# 1_Connector.net
KiCad netlist of a schematic drawn in Altium Designer
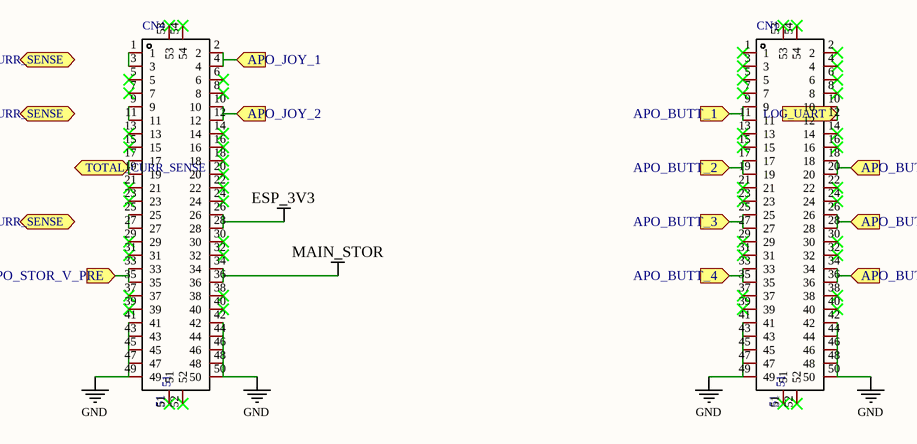
[diagram p0: 1_Connector.schdoc]

(export (version "E")
  (design (tool "Eeschema 10.0.6"))
  (components
    (comp (ref "CN1")
      (value "DF40C-50DP-0.4V(51)")
      (fields (field (name "MANUFACTURER") "HRS(广濑)") (field (name "NAME") "51") (field (name "NUMBER") "51"))
      (libsource (lib "altium-import") (part "root_0_DF40C-50DP-0.4V(51)_"))
    )
    (comp (ref "CN4")
      (value "DF40C-50DP-0.4V(51)")
      (fields (field (name "MANUFACTURER") "HRS(广濑)") (field (name "NAME") "51") (field (name "NUMBER") "51"))
      (libsource (lib "altium-import") (part "root_0_DF40C-50DP-0.4V(51)_"))
    )
  )
  (nets
    (net (code "1") (name "/APO_BUTT_1") (class "Default")
      (node (ref "CN1") (pin "11") (pinfunction "11_11") (pintype "passive"))
      (node (ref "CN1") (pin "9") (pinfunction "9_9") (pintype "passive"))
    )
    (net (code "2") (name "/APO_BUTT_2") (class "Default")
      (node (ref "CN1") (pin "17") (pinfunction "17_17") (pintype "passive"))
      (node (ref "CN1") (pin "19") (pinfunction "19_19") (pintype "passive"))
    )
    (net (code "3") (name "/APO_BUTT_3") (class "Default")
      (node (ref "CN1") (pin "25") (pinfunction "25_25") (pintype "passive"))
      (node (ref "CN1") (pin "27") (pinfunction "27_27") (pintype "passive"))
    )
    (net (code "4") (name "/APO_BUTT_4") (class "Default")
      (node (ref "CN1") (pin "33") (pinfunction "33_33") (pintype "passive"))
      (node (ref "CN1") (pin "35") (pinfunction "35_35") (pintype "passive"))
    )
    (net (code "5") (name "/APO_BUTT_5") (class "Default")
      (node (ref "CN1") (pin "34") (pinfunction "34_34") (pintype "passive"))
      (node (ref "CN1") (pin "36") (pinfunction "36_36") (pintype "passive"))
    )
    (net (code "6") (name "/APO_BUTT_6") (class "Default")
      (node (ref "CN1") (pin "26") (pinfunction "26_26") (pintype "passive"))
      (node (ref "CN1") (pin "28") (pinfunction "28_28") (pintype "passive"))
    )
    (net (code "7") (name "/APO_BUTT_7") (class "Default")
      (node (ref "CN1") (pin "18") (pinfunction "18_18") (pintype "passive"))
      (node (ref "CN1") (pin "20") (pinfunction "20_20") (pintype "passive"))
    )
    (net (code "8") (name "/APO_JOY_1") (class "Default")
      (node (ref "CN4") (pin "2") (pinfunction "2_2") (pintype "passive"))
      (node (ref "CN4") (pin "4") (pinfunction "4_4") (pintype "passive"))
    )
    (net (code "9") (name "/APO_JOY_2") (class "Default")
      (node (ref "CN4") (pin "10") (pinfunction "10_10") (pintype "passive"))
      (node (ref "CN4") (pin "12") (pinfunction "12_12") (pintype "passive"))
    )
    (net (code "10") (name "/APO_STOR_V_PRE") (class "Default")
      (node (ref "CN4") (pin "33") (pinfunction "33_33") (pintype "passive"))
      (node (ref "CN4") (pin "35") (pinfunction "35_35") (pintype "passive"))
    )
    (net (code "13") (name "/LOG_UART") (class "Default")
      (node (ref "CN1") (pin "10") (pinfunction "10_10") (pintype "passive"))
      (node (ref "CN1") (pin "12") (pinfunction "12_12") (pintype "passive"))
    )
    (net (code "16") (name "ESP_3V3") (class "Default")
      (node (ref "CN4") (pin "26") (pinfunction "26_26") (pintype "passive"))
      (node (ref "CN4") (pin "28") (pinfunction "28_28") (pintype "passive"))
    )
    (net (code "17") (name "GND") (class "Default")
      (node (ref "CN1") (pin "41") (pinfunction "41_41") (pintype "passive"))
      (node (ref "CN1") (pin "42") (pinfunction "42_42") (pintype "passive"))
      (node (ref "CN1") (pin "43") (pinfunction "43_43") (pintype "passive"))
      (node (ref "CN1") (pin "44") (pinfunction "44_44") (pintype "passive"))
      (node (ref "CN1") (pin "45") (pinfunction "45_45") (pintype "passive"))
      (node (ref "CN1") (pin "46") (pinfunction "46_46") (pintype "passive"))
      (node (ref "CN1") (pin "47") (pinfunction "47_47") (pintype "passive"))
      (node (ref "CN1") (pin "48") (pinfunction "48_48") (pintype "passive"))
      (node (ref "CN1") (pin "49") (pinfunction "49_49") (pintype "passive"))
      (node (ref "CN1") (pin "50") (pinfunction "50_50") (pintype "passive"))
      (node (ref "CN4") (pin "41") (pinfunction "41_41") (pintype "passive"))
      (node (ref "CN4") (pin "42") (pinfunction "42_42") (pintype "passive"))
      (node (ref "CN4") (pin "43") (pinfunction "43_43") (pintype "passive"))
      (node (ref "CN4") (pin "44") (pinfunction "44_44") (pintype "passive"))
      (node (ref "CN4") (pin "45") (pinfunction "45_45") (pintype "passive"))
      (node (ref "CN4") (pin "46") (pinfunction "46_46") (pintype "passive"))
      (node (ref "CN4") (pin "47") (pinfunction "47_47") (pintype "passive"))
      (node (ref "CN4") (pin "48") (pinfunction "48_48") (pintype "passive"))
      (node (ref "CN4") (pin "49") (pinfunction "49_49") (pintype "passive"))
      (node (ref "CN4") (pin "50") (pinfunction "50_50") (pintype "passive"))
    )
    (net (code "18") (name "MAIN_STOR") (class "Default")
      (node (ref "CN4") (pin "34") (pinfunction "34_34") (pintype "passive"))
      (node (ref "CN4") (pin "36") (pinfunction "36_36") (pintype "passive"))
    )
    (net (code "19") (name "Net-(CN4-Pad1)") (class "Default")
      (node (ref "CN4") (pin "1") (pinfunction "1_1") (pintype "passive"))
      (node (ref "CN4") (pin "3") (pinfunction "3_3") (pintype "passive"))
    )
    (net (code "20") (name "Net-(CN4-Pad11)") (class "Default")
      (node (ref "CN4") (pin "11") (pinfunction "11_11") (pintype "passive"))
      (node (ref "CN4") (pin "9") (pinfunction "9_9") (pintype "passive"))
    )
    (net (code "21") (name "Net-(CN4-Pad17)") (class "Default")
      (node (ref "CN4") (pin "17") (pinfunction "17_17") (pintype "passive"))
      (node (ref "CN4") (pin "19") (pinfunction "19_19") (pintype "passive"))
    )
    (net (code "22") (name "Net-(CN4-Pad25)") (class "Default")
      (node (ref "CN4") (pin "25") (pinfunction "25_25") (pintype "passive"))
      (node (ref "CN4") (pin "27") (pinfunction "27_27") (pintype "passive"))
    )
    (net (code "23") (name "unconnected-(CN1-Pad1)") (class "Default")
      (node (ref "CN1") (pin "1") (pinfunction "1_1") (pintype "passive+no_connect"))
    )
    (net (code "24") (name "unconnected-(CN1-Pad2)") (class "Default")
      (node (ref "CN1") (pin "2") (pinfunction "2_2") (pintype "passive+no_connect"))
    )
    (net (code "25") (name "unconnected-(CN1-Pad3)") (class "Default")
      (node (ref "CN1") (pin "3") (pinfunction "3_3") (pintype "passive+no_connect"))
    )
    (net (code "26") (name "unconnected-(CN1-Pad4)") (class "Default")
      (node (ref "CN1") (pin "4") (pinfunction "4_4") (pintype "passive+no_connect"))
    )
    (net (code "27") (name "unconnected-(CN1-Pad5)") (class "Default")
      (node (ref "CN1") (pin "5") (pinfunction "5_5") (pintype "passive+no_connect"))
    )
    (net (code "28") (name "unconnected-(CN1-Pad6)") (class "Default")
      (node (ref "CN1") (pin "6") (pinfunction "6_6") (pintype "passive+no_connect"))
    )
    (net (code "29") (name "unconnected-(CN1-Pad7)") (class "Default")
      (node (ref "CN1") (pin "7") (pinfunction "7_7") (pintype "passive+no_connect"))
    )
    (net (code "30") (name "unconnected-(CN1-Pad8)") (class "Default")
      (node (ref "CN1") (pin "8") (pinfunction "8_8") (pintype "passive+no_connect"))
    )
    (net (code "31") (name "unconnected-(CN1-Pad13)") (class "Default")
      (node (ref "CN1") (pin "13") (pinfunction "13_13") (pintype "passive+no_connect"))
    )
    (net (code "32") (name "unconnected-(CN1-Pad14)") (class "Default")
      (node (ref "CN1") (pin "14") (pinfunction "14_14") (pintype "passive+no_connect"))
    )
    (net (code "33") (name "unconnected-(CN1-Pad15)") (class "Default")
      (node (ref "CN1") (pin "15") (pinfunction "15_15") (pintype "passive+no_connect"))
    )
    (net (code "34") (name "unconnected-(CN1-Pad16)") (class "Default")
      (node (ref "CN1") (pin "16") (pinfunction "16_16") (pintype "passive+no_connect"))
    )
    (net (code "35") (name "unconnected-(CN1-Pad21)") (class "Default")
      (node (ref "CN1") (pin "21") (pinfunction "21_21") (pintype "passive+no_connect"))
    )
    (net (code "36") (name "unconnected-(CN1-Pad22)") (class "Default")
      (node (ref "CN1") (pin "22") (pinfunction "22_22") (pintype "passive+no_connect"))
    )
    (net (code "37") (name "unconnected-(CN1-Pad23)") (class "Default")
      (node (ref "CN1") (pin "23") (pinfunction "23_23") (pintype "passive+no_connect"))
    )
    (net (code "38") (name "unconnected-(CN1-Pad24)") (class "Default")
      (node (ref "CN1") (pin "24") (pinfunction "24_24") (pintype "passive+no_connect"))
    )
    (net (code "39") (name "unconnected-(CN1-Pad29)") (class "Default")
      (node (ref "CN1") (pin "29") (pinfunction "29_29") (pintype "passive+no_connect"))
    )
    (net (code "40") (name "unconnected-(CN1-Pad30)") (class "Default")
      (node (ref "CN1") (pin "30") (pinfunction "30_30") (pintype "passive+no_connect"))
    )
    (net (code "41") (name "unconnected-(CN1-Pad31)") (class "Default")
      (node (ref "CN1") (pin "31") (pinfunction "31_31") (pintype "passive+no_connect"))
    )
    (net (code "42") (name "unconnected-(CN1-Pad32)") (class "Default")
      (node (ref "CN1") (pin "32") (pinfunction "32_32") (pintype "passive+no_connect"))
    )
    (net (code "43") (name "unconnected-(CN1-Pad37)") (class "Default")
      (node (ref "CN1") (pin "37") (pinfunction "37_37") (pintype "passive+no_connect"))
    )
    (net (code "44") (name "unconnected-(CN1-Pad38)") (class "Default")
      (node (ref "CN1") (pin "38") (pinfunction "38_38") (pintype "passive+no_connect"))
    )
    (net (code "45") (name "unconnected-(CN1-Pad39)") (class "Default")
      (node (ref "CN1") (pin "39") (pinfunction "39_39") (pintype "passive+no_connect"))
    )
    (net (code "46") (name "unconnected-(CN1-Pad40)") (class "Default")
      (node (ref "CN1") (pin "40") (pinfunction "40_40") (pintype "passive+no_connect"))
    )
    (net (code "47") (name "unconnected-(CN1-Pad51)") (class "Default")
      (node (ref "CN1") (pin "51") (pinfunction "51_51") (pintype "passive+no_connect"))
    )
    (net (code "48") (name "unconnected-(CN1-Pad52)") (class "Default")
      (node (ref "CN1") (pin "52") (pinfunction "52_52") (pintype "passive+no_connect"))
    )
    (net (code "49") (name "unconnected-(CN1-Pad53)") (class "Default")
      (node (ref "CN1") (pin "53") (pinfunction "53_53") (pintype "passive+no_connect"))
    )
    (net (code "50") (name "unconnected-(CN1-Pad54)") (class "Default")
      (node (ref "CN1") (pin "54") (pinfunction "54_54") (pintype "passive+no_connect"))
    )
    (net (code "51") (name "unconnected-(CN4-Pad5)") (class "Default")
      (node (ref "CN4") (pin "5") (pinfunction "5_5") (pintype "passive+no_connect"))
    )
    (net (code "52") (name "unconnected-(CN4-Pad6)") (class "Default")
      (node (ref "CN4") (pin "6") (pinfunction "6_6") (pintype "passive+no_connect"))
    )
    (net (code "53") (name "unconnected-(CN4-Pad7)") (class "Default")
      (node (ref "CN4") (pin "7") (pinfunction "7_7") (pintype "passive+no_connect"))
    )
    (net (code "54") (name "unconnected-(CN4-Pad8)") (class "Default")
      (node (ref "CN4") (pin "8") (pinfunction "8_8") (pintype "passive+no_connect"))
    )
    (net (code "55") (name "unconnected-(CN4-Pad13)") (class "Default")
      (node (ref "CN4") (pin "13") (pinfunction "13_13") (pintype "passive+no_connect"))
    )
    (net (code "56") (name "unconnected-(CN4-Pad14)") (class "Default")
      (node (ref "CN4") (pin "14") (pinfunction "14_14") (pintype "passive+no_connect"))
    )
    (net (code "57") (name "unconnected-(CN4-Pad15)") (class "Default")
      (node (ref "CN4") (pin "15") (pinfunction "15_15") (pintype "passive+no_connect"))
    )
    (net (code "58") (name "unconnected-(CN4-Pad16)") (class "Default")
      (node (ref "CN4") (pin "16") (pinfunction "16_16") (pintype "passive+no_connect"))
    )
    (net (code "59") (name "unconnected-(CN4-Pad18)") (class "Default")
      (node (ref "CN4") (pin "18") (pinfunction "18_18") (pintype "passive+no_connect"))
    )
    (net (code "60") (name "unconnected-(CN4-Pad20)") (class "Default")
      (node (ref "CN4") (pin "20") (pinfunction "20_20") (pintype "passive+no_connect"))
    )
    (net (code "61") (name "unconnected-(CN4-Pad21)") (class "Default")
      (node (ref "CN4") (pin "21") (pinfunction "21_21") (pintype "passive+no_connect"))
    )
    (net (code "62") (name "unconnected-(CN4-Pad22)") (class "Default")
      (node (ref "CN4") (pin "22") (pinfunction "22_22") (pintype "passive+no_connect"))
    )
    (net (code "63") (name "unconnected-(CN4-Pad23)") (class "Default")
      (node (ref "CN4") (pin "23") (pinfunction "23_23") (pintype "passive+no_connect"))
    )
    (net (code "64") (name "unconnected-(CN4-Pad24)") (class "Default")
      (node (ref "CN4") (pin "24") (pinfunction "24_24") (pintype "passive+no_connect"))
    )
    (net (code "65") (name "unconnected-(CN4-Pad29)") (class "Default")
      (node (ref "CN4") (pin "29") (pinfunction "29_29") (pintype "passive+no_connect"))
    )
    (net (code "66") (name "unconnected-(CN4-Pad30)") (class "Default")
      (node (ref "CN4") (pin "30") (pinfunction "30_30") (pintype "passive+no_connect"))
    )
    (net (code "67") (name "unconnected-(CN4-Pad31)") (class "Default")
      (node (ref "CN4") (pin "31") (pinfunction "31_31") (pintype "passive+no_connect"))
    )
    (net (code "68") (name "unconnected-(CN4-Pad32)") (class "Default")
      (node (ref "CN4") (pin "32") (pinfunction "32_32") (pintype "passive+no_connect"))
    )
    (net (code "69") (name "unconnected-(CN4-Pad37)") (class "Default")
      (node (ref "CN4") (pin "37") (pinfunction "37_37") (pintype "passive+no_connect"))
    )
    (net (code "70") (name "unconnected-(CN4-Pad38)") (class "Default")
      (node (ref "CN4") (pin "38") (pinfunction "38_38") (pintype "passive+no_connect"))
    )
    (net (code "71") (name "unconnected-(CN4-Pad39)") (class "Default")
      (node (ref "CN4") (pin "39") (pinfunction "39_39") (pintype "passive+no_connect"))
    )
    (net (code "72") (name "unconnected-(CN4-Pad40)") (class "Default")
      (node (ref "CN4") (pin "40") (pinfunction "40_40") (pintype "passive+no_connect"))
    )
    (net (code "73") (name "unconnected-(CN4-Pad51)") (class "Default")
      (node (ref "CN4") (pin "51") (pinfunction "51_51") (pintype "passive+no_connect"))
    )
    (net (code "74") (name "unconnected-(CN4-Pad52)") (class "Default")
      (node (ref "CN4") (pin "52") (pinfunction "52_52") (pintype "passive+no_connect"))
    )
    (net (code "75") (name "unconnected-(CN4-Pad53)") (class "Default")
      (node (ref "CN4") (pin "53") (pinfunction "53_53") (pintype "passive+no_connect"))
    )
    (net (code "76") (name "unconnected-(CN4-Pad54)") (class "Default")
      (node (ref "CN4") (pin "54") (pinfunction "54_54") (pintype "passive+no_connect"))
    )
  )
)
